# oneboard5.net
KiCad netlist of a schematic drawn in EAGLE
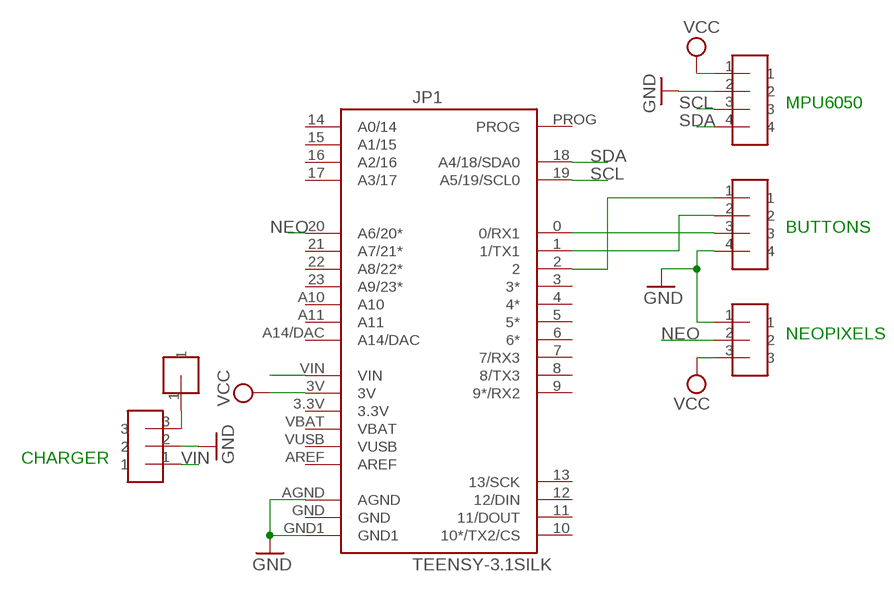
[diagram p0: schematic, sheet 1]

(export (version "E")
  (design (tool "Eeschema 10.0.6"))
  (components
    (comp (ref "JP1")
      (value "TEENSY-3.1SILK")
      (footprint "eagle-import:TEENSY-3.1")
      (libsource (lib "eagle-import") (part "TEENSY-3.1SILK"))
    )
    (comp (ref "U$1")
      (value "HEADER-3")
      (footprint "eagle-import:HEADER-3")
      (libsource (lib "eagle-import") (part "HEADER-3"))
    )
    (comp (ref "U$2")
      (value "HEADER-3")
      (footprint "eagle-import:HEADER-3")
      (libsource (lib "eagle-import") (part "HEADER-3"))
    )
    (comp (ref "U$3")
      (value "HEADER-1")
      (footprint "eagle-import:HEADER-1")
      (libsource (lib "eagle-import") (part "HEADER-1"))
    )
    (comp (ref "U$4")
      (value "HEADER-4")
      (footprint "eagle-import:HEADER-4")
      (libsource (lib "eagle-import") (part "HEADER-4"))
    )
    (comp (ref "U$5")
      (value "HEADER-4")
      (footprint "eagle-import:HEADER-4")
      (libsource (lib "eagle-import") (part "HEADER-4"))
    )
  )
  (nets
    (net (code "1") (name "/NEO") (class "Default")
      (node (ref "JP1") (pin "20") (pinfunction "A6/20*_20") (pintype "bidirectional"))
      (node (ref "U$2") (pin "2") (pinfunction "2_2") (pintype "bidirectional"))
    )
    (net (code "2") (name "/SCL") (class "Default")
      (node (ref "JP1") (pin "19") (pinfunction "A5/19/SCL0_19") (pintype "bidirectional"))
      (node (ref "U$4") (pin "3") (pinfunction "3_3") (pintype "bidirectional"))
    )
    (net (code "3") (name "/SDA") (class "Default")
      (node (ref "JP1") (pin "18") (pinfunction "A4/18/SDA0_18") (pintype "bidirectional"))
      (node (ref "U$4") (pin "4") (pinfunction "4_4") (pintype "bidirectional"))
    )
    (net (code "4") (name "/VIN") (class "Default")
      (node (ref "JP1") (pin "VIN") (pinfunction "VIN_VIN") (pintype "bidirectional"))
      (node (ref "U$1") (pin "1") (pinfunction "1_1") (pintype "bidirectional"))
    )
    (net (code "5") (name "GND") (class "Default")
      (node (ref "JP1") (pin "AGND") (pinfunction "AGND_AGND") (pintype "bidirectional"))
      (node (ref "JP1") (pin "GND1") (pinfunction "GND1_GND1") (pintype "bidirectional"))
      (node (ref "U$1") (pin "2") (pinfunction "2_2") (pintype "bidirectional"))
      (node (ref "U$2") (pin "1") (pinfunction "1_1") (pintype "bidirectional"))
      (node (ref "U$4") (pin "2") (pinfunction "2_2") (pintype "bidirectional"))
      (node (ref "U$5") (pin "4") (pinfunction "4_4") (pintype "bidirectional"))
    )
    (net (code "6") (name "Net-(JP1-0{slash}RX1)") (class "Default")
      (node (ref "JP1") (pin "0") (pinfunction "0/RX1_0") (pintype "bidirectional"))
      (node (ref "U$5") (pin "3") (pinfunction "3_3") (pintype "bidirectional"))
    )
    (net (code "7") (name "Net-(JP1-1{slash}TX1)") (class "Default")
      (node (ref "JP1") (pin "1") (pinfunction "1/TX1_1") (pintype "bidirectional"))
      (node (ref "U$5") (pin "2") (pinfunction "2_2") (pintype "bidirectional"))
    )
    (net (code "8") (name "Net-(JP1-Pad2)") (class "Default")
      (node (ref "JP1") (pin "2") (pinfunction "2_2") (pintype "bidirectional"))
      (node (ref "U$5") (pin "1") (pinfunction "1_1") (pintype "bidirectional"))
    )
    (net (code "9") (name "Net-(U$1-Pad3)") (class "Default")
      (node (ref "U$1") (pin "3") (pinfunction "3_3") (pintype "bidirectional"))
      (node (ref "U$3") (pin "1") (pinfunction "1_1") (pintype "bidirectional"))
    )
    (net (code "10") (name "VCC") (class "Default")
      (node (ref "JP1") (pin "3V") (pinfunction "3V_3V") (pintype "bidirectional"))
      (node (ref "U$2") (pin "3") (pinfunction "3_3") (pintype "bidirectional"))
      (node (ref "U$4") (pin "1") (pinfunction "1_1") (pintype "bidirectional"))
    )
    (net (code "11") (name "unconnected-(JP1-3*-Pad3)") (class "Default")
      (node (ref "JP1") (pin "3") (pinfunction "3*_3") (pintype "bidirectional"))
    )
    (net (code "12") (name "unconnected-(JP1-4*-Pad4)") (class "Default")
      (node (ref "JP1") (pin "4") (pinfunction "4*_4") (pintype "bidirectional"))
    )
    (net (code "13") (name "unconnected-(JP1-5*-Pad5)") (class "Default")
      (node (ref "JP1") (pin "5") (pinfunction "5*_5") (pintype "bidirectional"))
    )
    (net (code "14") (name "unconnected-(JP1-6*-Pad6)") (class "Default")
      (node (ref "JP1") (pin "6") (pinfunction "6*_6") (pintype "bidirectional"))
    )
    (net (code "15") (name "unconnected-(JP1-7{slash}RX3-Pad7)") (class "Default")
      (node (ref "JP1") (pin "7") (pinfunction "7/RX3_7") (pintype "bidirectional"))
    )
    (net (code "16") (name "unconnected-(JP1-8{slash}TX3-Pad8)") (class "Default")
      (node (ref "JP1") (pin "8") (pinfunction "8/TX3_8") (pintype "bidirectional"))
    )
    (net (code "17") (name "unconnected-(JP1-9*{slash}RX2-Pad9)") (class "Default")
      (node (ref "JP1") (pin "9") (pinfunction "9*/RX2_9") (pintype "bidirectional"))
    )
    (net (code "18") (name "unconnected-(JP1-10*{slash}TX2{slash}CS-Pad10)") (class "Default")
      (node (ref "JP1") (pin "10") (pinfunction "10*/TX2/CS_10") (pintype "bidirectional"))
    )
    (net (code "19") (name "unconnected-(JP1-11{slash}DOUT-Pad11)") (class "Default")
      (node (ref "JP1") (pin "11") (pinfunction "11/DOUT_11") (pintype "bidirectional"))
    )
    (net (code "20") (name "unconnected-(JP1-12{slash}DIN-Pad12)") (class "Default")
      (node (ref "JP1") (pin "12") (pinfunction "12/DIN_12") (pintype "bidirectional"))
    )
    (net (code "21") (name "unconnected-(JP1-13{slash}SCK-Pad13)") (class "Default")
      (node (ref "JP1") (pin "13") (pinfunction "13/SCK_13") (pintype "bidirectional"))
    )
    (net (code "22") (name "unconnected-(JP1-A0{slash}14-Pad14)") (class "Default")
      (node (ref "JP1") (pin "14") (pinfunction "A0/14_14") (pintype "bidirectional"))
    )
    (net (code "23") (name "unconnected-(JP1-A1{slash}15-Pad15)") (class "Default")
      (node (ref "JP1") (pin "15") (pinfunction "A1/15_15") (pintype "bidirectional"))
    )
    (net (code "24") (name "unconnected-(JP1-A2{slash}16-Pad16)") (class "Default")
      (node (ref "JP1") (pin "16") (pinfunction "A2/16_16") (pintype "bidirectional"))
    )
    (net (code "25") (name "unconnected-(JP1-A3{slash}17-Pad17)") (class "Default")
      (node (ref "JP1") (pin "17") (pinfunction "A3/17_17") (pintype "bidirectional"))
    )
    (net (code "26") (name "unconnected-(JP1-A7{slash}21*-Pad21)") (class "Default")
      (node (ref "JP1") (pin "21") (pinfunction "A7/21*_21") (pintype "bidirectional"))
    )
    (net (code "27") (name "unconnected-(JP1-A8{slash}22*-Pad22)") (class "Default")
      (node (ref "JP1") (pin "22") (pinfunction "A8/22*_22") (pintype "bidirectional"))
    )
    (net (code "28") (name "unconnected-(JP1-A9{slash}23*-Pad23)") (class "Default")
      (node (ref "JP1") (pin "23") (pinfunction "A9/23*_23") (pintype "bidirectional"))
    )
    (net (code "29") (name "unconnected-(JP1-Pad3.3V)") (class "Default")
      (node (ref "JP1") (pin "3.3V") (pinfunction "3.3V_3.3V") (pintype "bidirectional"))
    )
    (net (code "30") (name "unconnected-(JP1-PadA10)") (class "Default")
      (node (ref "JP1") (pin "A10") (pinfunction "A10_A10") (pintype "bidirectional"))
    )
    (net (code "31") (name "unconnected-(JP1-PadA11)") (class "Default")
      (node (ref "JP1") (pin "A11") (pinfunction "A11_A11") (pintype "bidirectional"))
    )
    (net (code "32") (name "unconnected-(JP1-PadA14{slash}DAC)") (class "Default")
      (node (ref "JP1") (pin "A14/DAC") (pinfunction "A14/DAC_A14/DAC") (pintype "bidirectional"))
    )
    (net (code "33") (name "unconnected-(JP1-PadAREF)") (class "Default")
      (node (ref "JP1") (pin "AREF") (pinfunction "AREF_AREF") (pintype "bidirectional"))
    )
    (net (code "34") (name "unconnected-(JP1-PadGND)") (class "Default")
      (node (ref "JP1") (pin "GND") (pinfunction "GND_GND") (pintype "bidirectional"))
    )
    (net (code "35") (name "unconnected-(JP1-PadPROG)") (class "Default")
      (node (ref "JP1") (pin "PROG") (pinfunction "PROG_PROG") (pintype "bidirectional"))
    )
    (net (code "36") (name "unconnected-(JP1-PadVBAT)") (class "Default")
      (node (ref "JP1") (pin "VBAT") (pinfunction "VBAT_VBAT") (pintype "bidirectional"))
    )
    (net (code "37") (name "unconnected-(JP1-PadVUSB)") (class "Default")
      (node (ref "JP1") (pin "VUSB") (pinfunction "VUSB_VUSB") (pintype "bidirectional"))
    )
  )
)
